# controller.net
KiCad netlist of a schematic drawn in Altium Designer
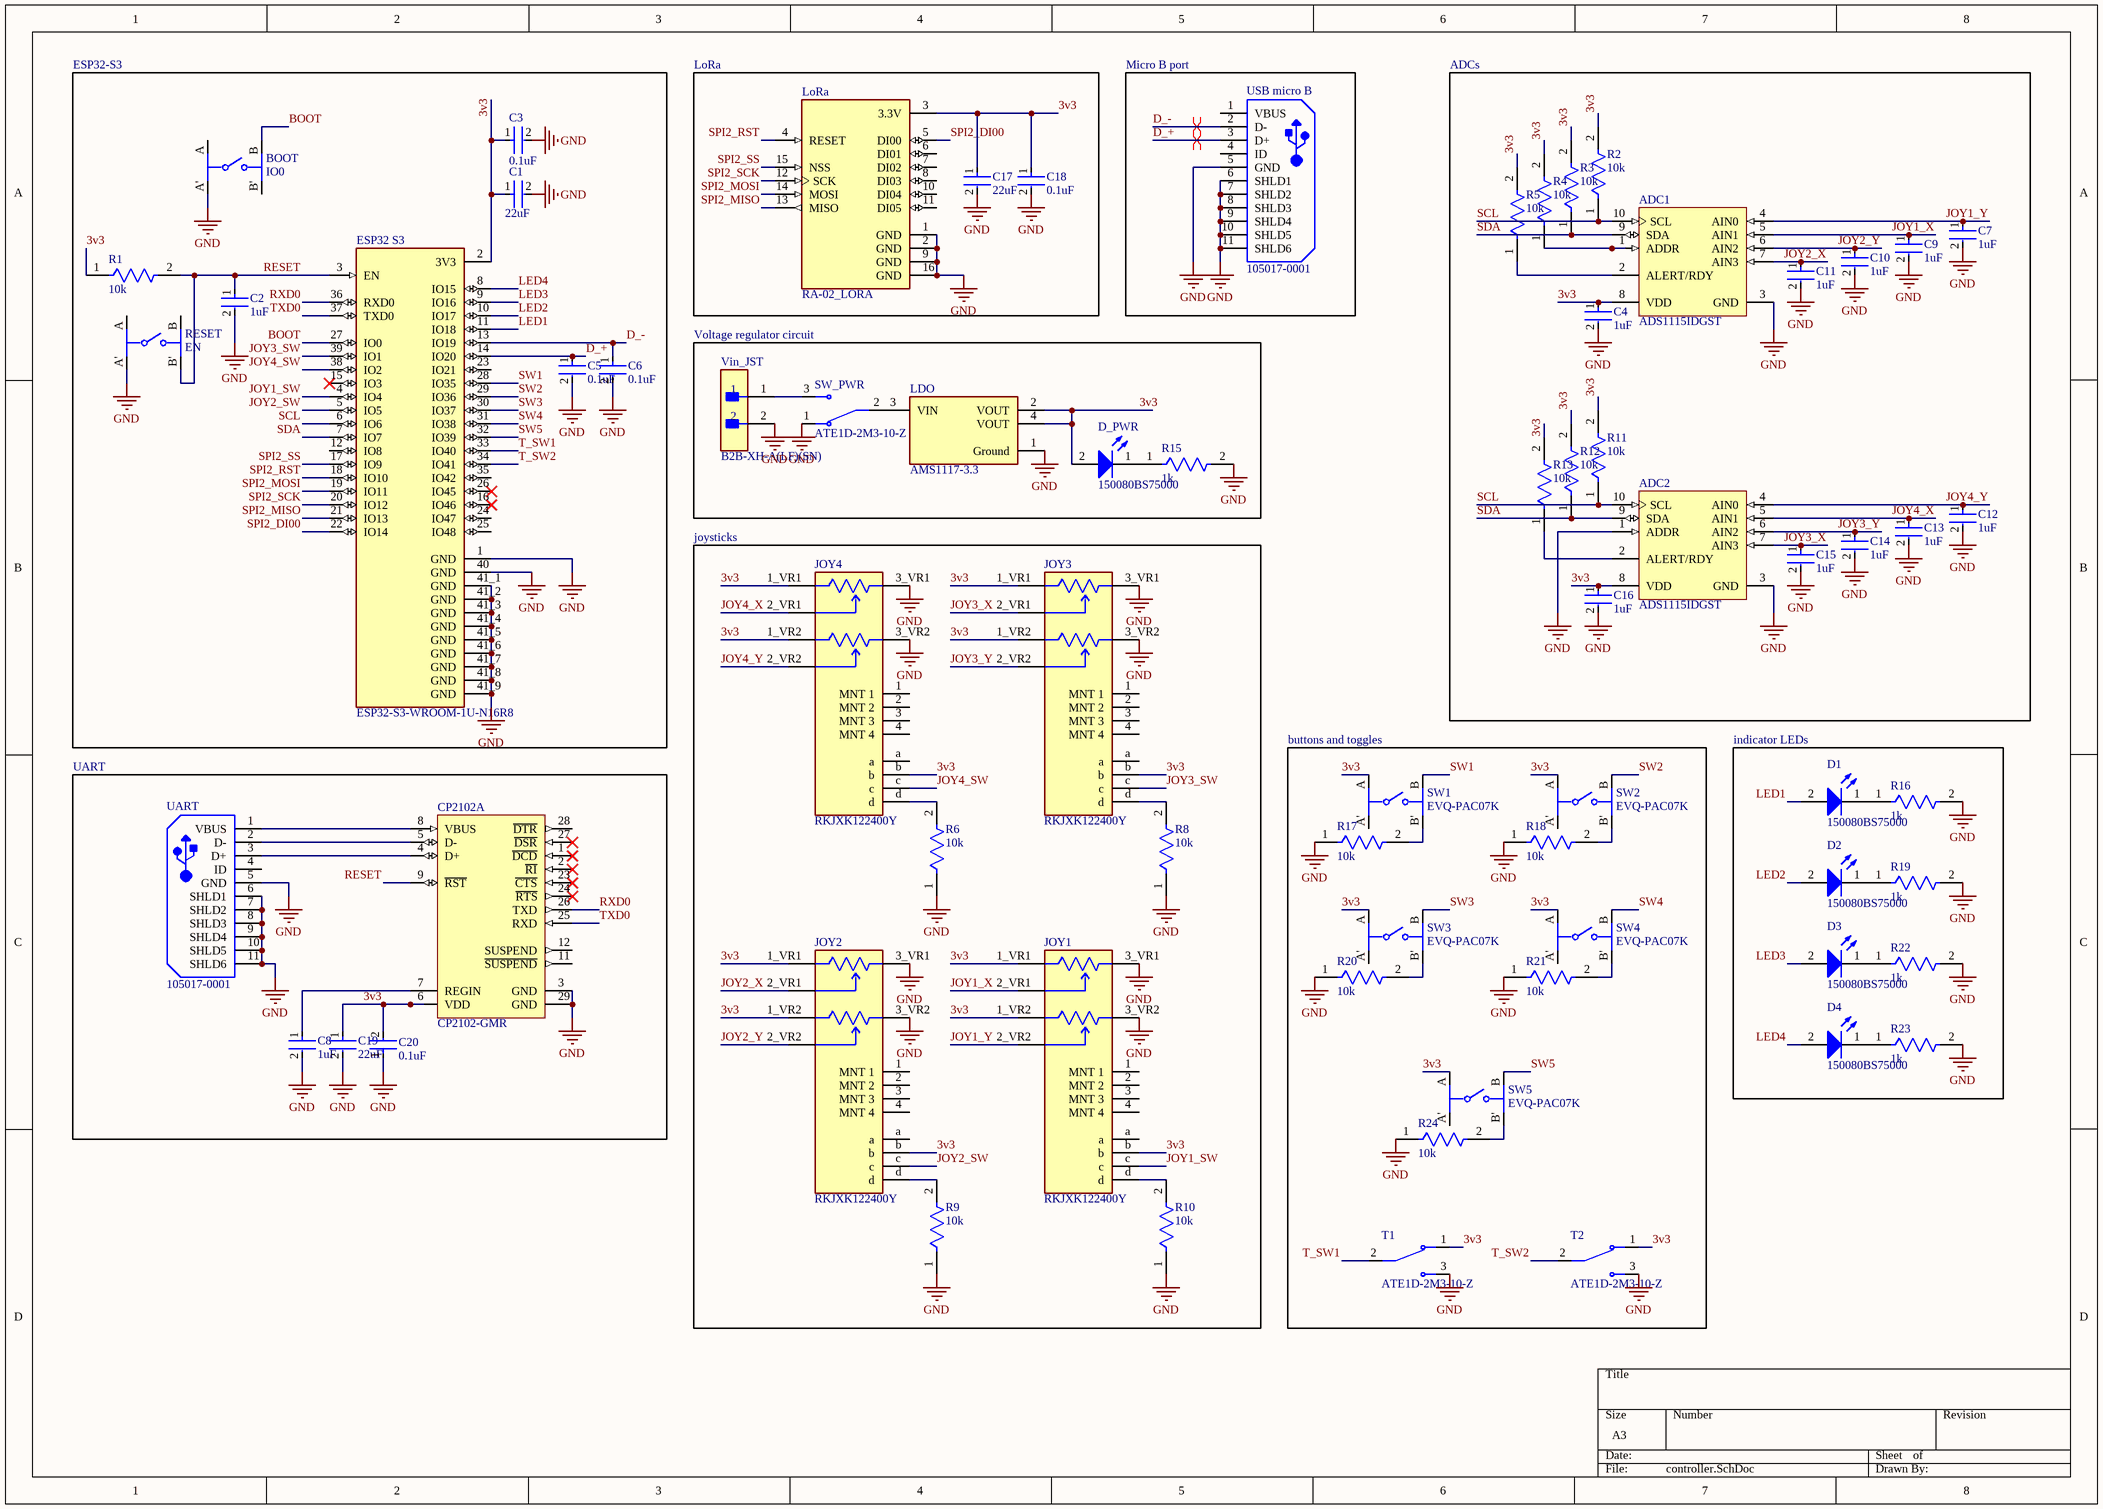
[diagram p0: controller.SchDoc]

(export (version "E")
  (design (tool "Eeschema 10.0.6"))
  (components
    (comp (ref "ADC1")
      (value "ADS1115IDGST")
      (footprint "TI-DGS10_M")
      (fields (field (name "MANUFACTURER") "Texas Instruments"))
      (libsource (lib "Altium Content Vault") (part "TI-ADS1015_1115-10"))
    )
    (comp (ref "ADC2")
      (value "ADS1115IDGST")
      (footprint "TI-DGS10_M")
      (fields (field (name "MANUFACTURER") "Texas Instruments"))
      (libsource (lib "Altium Content Vault") (part "TI-ADS1015_1115-10"))
    )
    (comp (ref "BOOT")
      (value "IO0")
      (footprint "FP-EVQ-PAC07K-MFG")
      (description "EVQ-PAC07K Switch Tactile N.O. SPST Round Button PC Pins 0.02A 15VDC 1N Thru-Hole Bulk")
      (libsource (lib "Altium Content Vault") (part "841f23923f71b23f3ea0ab5dfb78dcc"))
    )
    (comp (ref "C1")
      (value "22uF")
      (footprint "FP-0805-L_2_01_0_2-W_1_25-IPC_B")
      (description "General Purpose Ceramic Capacitor, 0805, 22uF, 20%, X5R, 15%, 6.3V")
      (fields (field (name "TOLERANCE") "20%") (field (name "VOLTAGE") "6.3V"))
      (libsource (lib "Altium Content Vault") (part "02cd4be3c70576c341d710602a673aa"))
    )
    (comp (ref "C2")
      (value "1uF")
      (footprint "FP-0805-L_2_01_0_2-W_1_25-IPC_B")
      (description "General Purpose Ceramic Capacitor, 0805, 1uF, 10%, X7R, 15%, 25V")
      (fields (field (name "TOLERANCE") "10%") (field (name "VOLTAGE") "25V"))
      (libsource (lib "Altium Content Vault") (part "b4654b650e69147ec39a6b967a45e02"))
    )
    (comp (ref "C3")
      (value "0.1uF")
      (footprint "FP-0805-L_2_01_0_2-W_1_25-IPC_C")
      (description "General Purpose Ceramic Capacitor, 0805, 100nF, 10%, X7R, 0.15, 50V")
      (fields (field (name "TOLERANCE") "10%") (field (name "VOLTAGE") "50V"))
      (libsource (lib "Altium Content Vault") (part "02cd4be3c70576c341d710602a673aa"))
    )
    (comp (ref "C4")
      (value "1uF")
      (footprint "FP-0805-L_2_01_0_2-W_1_25-IPC_B")
      (description "General Purpose Ceramic Capacitor, 0805, 1uF, 10%, X7R, 15%, 25V")
      (fields (field (name "TOLERANCE") "10%") (field (name "VOLTAGE") "25V"))
      (libsource (lib "Altium Content Vault") (part "b4654b650e69147ec39a6b967a45e02"))
    )
    (comp (ref "C5")
      (value "0.1uF")
      (footprint "FP-0805-L_2_01_0_2-W_1_25-IPC_C")
      (description "General Purpose Ceramic Capacitor, 0805, 100nF, 10%, X7R, 0.15, 50V")
      (fields (field (name "TOLERANCE") "10%") (field (name "VOLTAGE") "50V"))
      (libsource (lib "Altium Content Vault") (part "02cd4be3c70576c341d710602a673aa"))
    )
    (comp (ref "C6")
      (value "0.1uF")
      (footprint "FP-0805-L_2_01_0_2-W_1_25-IPC_C")
      (description "General Purpose Ceramic Capacitor, 0805, 100nF, 10%, X7R, 0.15, 50V")
      (fields (field (name "TOLERANCE") "10%") (field (name "VOLTAGE") "50V"))
      (libsource (lib "Altium Content Vault") (part "02cd4be3c70576c341d710602a673aa"))
    )
    (comp (ref "C7")
      (value "1uF")
      (footprint "FP-0805-L_2_01_0_2-W_1_25-IPC_B")
      (description "General Purpose Ceramic Capacitor, 0805, 1uF, 10%, X7R, 15%, 25V")
      (fields (field (name "TOLERANCE") "10%") (field (name "VOLTAGE") "25V"))
      (libsource (lib "Altium Content Vault") (part "b4654b650e69147ec39a6b967a45e02"))
    )
    (comp (ref "C8")
      (value "1uF")
      (footprint "FP-0805-L_2_01_0_2-W_1_25-IPC_B")
      (description "General Purpose Ceramic Capacitor, 0805, 1uF, 10%, X7R, 15%, 25V")
      (fields (field (name "TOLERANCE") "10%") (field (name "VOLTAGE") "25V"))
      (libsource (lib "Altium Content Vault") (part "b4654b650e69147ec39a6b967a45e02"))
    )
    (comp (ref "C9")
      (value "1uF")
      (footprint "FP-0805-L_2_01_0_2-W_1_25-IPC_B")
      (description "General Purpose Ceramic Capacitor, 0805, 1uF, 10%, X7R, 15%, 25V")
      (fields (field (name "TOLERANCE") "10%") (field (name "VOLTAGE") "25V"))
      (libsource (lib "Altium Content Vault") (part "b4654b650e69147ec39a6b967a45e02"))
    )
    (comp (ref "C10")
      (value "1uF")
      (footprint "FP-0805-L_2_01_0_2-W_1_25-IPC_B")
      (description "General Purpose Ceramic Capacitor, 0805, 1uF, 10%, X7R, 15%, 25V")
      (fields (field (name "TOLERANCE") "10%") (field (name "VOLTAGE") "25V"))
      (libsource (lib "Altium Content Vault") (part "b4654b650e69147ec39a6b967a45e02"))
    )
    (comp (ref "C11")
      (value "1uF")
      (footprint "FP-0805-L_2_01_0_2-W_1_25-IPC_B")
      (description "General Purpose Ceramic Capacitor, 0805, 1uF, 10%, X7R, 15%, 25V")
      (fields (field (name "TOLERANCE") "10%") (field (name "VOLTAGE") "25V"))
      (libsource (lib "Altium Content Vault") (part "b4654b650e69147ec39a6b967a45e02"))
    )
    (comp (ref "C12")
      (value "1uF")
      (footprint "FP-0805-L_2_01_0_2-W_1_25-IPC_B")
      (description "General Purpose Ceramic Capacitor, 0805, 1uF, 10%, X7R, 15%, 25V")
      (fields (field (name "TOLERANCE") "10%") (field (name "VOLTAGE") "25V"))
      (libsource (lib "Altium Content Vault") (part "b4654b650e69147ec39a6b967a45e02"))
    )
    (comp (ref "C13")
      (value "1uF")
      (footprint "FP-0805-L_2_01_0_2-W_1_25-IPC_B")
      (description "General Purpose Ceramic Capacitor, 0805, 1uF, 10%, X7R, 15%, 25V")
      (fields (field (name "TOLERANCE") "10%") (field (name "VOLTAGE") "25V"))
      (libsource (lib "Altium Content Vault") (part "b4654b650e69147ec39a6b967a45e02"))
    )
    (comp (ref "C14")
      (value "1uF")
      (footprint "FP-0805-L_2_01_0_2-W_1_25-IPC_B")
      (description "General Purpose Ceramic Capacitor, 0805, 1uF, 10%, X7R, 15%, 25V")
      (fields (field (name "TOLERANCE") "10%") (field (name "VOLTAGE") "25V"))
      (libsource (lib "Altium Content Vault") (part "b4654b650e69147ec39a6b967a45e02"))
    )
    (comp (ref "C15")
      (value "1uF")
      (footprint "FP-0805-L_2_01_0_2-W_1_25-IPC_B")
      (description "General Purpose Ceramic Capacitor, 0805, 1uF, 10%, X7R, 15%, 25V")
      (fields (field (name "TOLERANCE") "10%") (field (name "VOLTAGE") "25V"))
      (libsource (lib "Altium Content Vault") (part "b4654b650e69147ec39a6b967a45e02"))
    )
    (comp (ref "C16")
      (value "1uF")
      (footprint "FP-0805-L_2_01_0_2-W_1_25-IPC_B")
      (description "General Purpose Ceramic Capacitor, 0805, 1uF, 10%, X7R, 15%, 25V")
      (fields (field (name "TOLERANCE") "10%") (field (name "VOLTAGE") "25V"))
      (libsource (lib "Altium Content Vault") (part "b4654b650e69147ec39a6b967a45e02"))
    )
    (comp (ref "C17")
      (value "22uF")
      (footprint "FP-0805-L_2_01_0_2-W_1_25-IPC_B")
      (description "General Purpose Ceramic Capacitor, 0805, 22uF, 20%, X5R, 15%, 6.3V")
      (fields (field (name "TOLERANCE") "20%") (field (name "VOLTAGE") "6.3V"))
      (libsource (lib "Altium Content Vault") (part "02cd4be3c70576c341d710602a673aa"))
    )
    (comp (ref "C18")
      (value "0.1uF")
      (footprint "FP-0805-L_2_01_0_2-W_1_25-IPC_C")
      (description "General Purpose Ceramic Capacitor, 0805, 100nF, 10%, X7R, 0.15, 50V")
      (fields (field (name "TOLERANCE") "10%") (field (name "VOLTAGE") "50V"))
      (libsource (lib "Altium Content Vault") (part "02cd4be3c70576c341d710602a673aa"))
    )
    (comp (ref "C19")
      (value "22uF")
      (footprint "FP-0805-L_2_01_0_2-W_1_25-IPC_B")
      (description "General Purpose Ceramic Capacitor, 0805, 22uF, 20%, X5R, 15%, 6.3V")
      (fields (field (name "TOLERANCE") "20%") (field (name "VOLTAGE") "6.3V"))
      (libsource (lib "Altium Content Vault") (part "02cd4be3c70576c341d710602a673aa"))
    )
    (comp (ref "C20")
      (value "0.1uF")
      (footprint "FP-0805-L_2_01_0_2-W_1_25-IPC_C")
      (description "General Purpose Ceramic Capacitor, 0805, 100nF, 10%, X7R, 0.15, 50V")
      (fields (field (name "TOLERANCE") "10%") (field (name "VOLTAGE") "50V"))
      (libsource (lib "Altium Content Vault") (part "02cd4be3c70576c341d710602a673aa"))
    )
    (comp (ref "CP2102")
      (value "CP2102-GMR")
      (footprint "SLAB-QFN-28-3125x3125TP_M")
      (description "Single-Chip USB to URAT Bridge, 3.3 V, -40 to 85 degC, 28-Pin QFN, RoHS, Tape and Reel")
      (fields (field (name "MANUFACTURER") "Silicon Labs"))
      (libsource (lib "Altium Content Vault") (part "SLAB-CP210X-QFN-28-29"))
    )
    (comp (ref "D1")
      (value "150080BS75000")
      (footprint "WL-SMCW_0805_150080xx75000")
      (description "Led, Blue, 470 Nm, 3.2 V, 30 Ma, 145 Mcd Rohs Compliant: Yes")
      (libsource (lib "Altium Content Vault") (part "LED_Blue_2A-1K"))
    )
    (comp (ref "D2")
      (value "150080BS75000")
      (footprint "WL-SMCW_0805_150080xx75000")
      (description "Led, Blue, 470 Nm, 3.2 V, 30 Ma, 145 Mcd Rohs Compliant: Yes")
      (libsource (lib "Altium Content Vault") (part "LED_Blue_2A-1K"))
    )
    (comp (ref "D3")
      (value "150080BS75000")
      (footprint "WL-SMCW_0805_150080xx75000")
      (description "Led, Blue, 470 Nm, 3.2 V, 30 Ma, 145 Mcd Rohs Compliant: Yes")
      (libsource (lib "Altium Content Vault") (part "LED_Blue_2A-1K"))
    )
    (comp (ref "D4")
      (value "150080BS75000")
      (footprint "WL-SMCW_0805_150080xx75000")
      (description "Led, Blue, 470 Nm, 3.2 V, 30 Ma, 145 Mcd Rohs Compliant: Yes")
      (libsource (lib "Altium Content Vault") (part "LED_Blue_2A-1K"))
    )
    (comp (ref "D_PWR")
      (value "150080BS75000")
      (footprint "WL-SMCW_0805_150080xx75000")
      (description "Led, Blue, 470 Nm, 3.2 V, 30 Ma, 145 Mcd Rohs Compliant: Yes")
      (libsource (lib "Altium Content Vault") (part "LED_Blue_2A-1K"))
    )
    (comp (ref "ESP32 S3")
      (value "ESP32-S3-WROOM-1U-N16R8")
      (footprint "XCVR_ESP32-S3-WROOM-1U-N16R8")
      (fields (field (name "MF") "Espressif Systems"))
      (libsource (lib "ESP32-S3-WROOM-1U-N16R8") (part "ESP32-S3-WROOM-1U-N16R8"))
    )
    (comp (ref "JOY1")
      (value "RKJXK122400Y")
      (footprint "FP-RKJXK122400Y-MFG")
      (description "Res POT 10K Ohm 0.0125W (25.4 X 20.7 X 19.3mm) Pin Bracket Mount/Through Hole Tray")
      (libsource (lib "Altium Content Vault") (part "63a56dd8e99e1e1552a3870b2e96c5c"))
    )
    (comp (ref "JOY2")
      (value "RKJXK122400Y")
      (footprint "FP-RKJXK122400Y-MFG")
      (description "Res POT 10K Ohm 0.0125W (25.4 X 20.7 X 19.3mm) Pin Bracket Mount/Through Hole Tray")
      (libsource (lib "Altium Content Vault") (part "63a56dd8e99e1e1552a3870b2e96c5c"))
    )
    (comp (ref "JOY3")
      (value "RKJXK122400Y")
      (footprint "FP-RKJXK122400Y-MFG")
      (description "Res POT 10K Ohm 0.0125W (25.4 X 20.7 X 19.3mm) Pin Bracket Mount/Through Hole Tray")
      (libsource (lib "Altium Content Vault") (part "63a56dd8e99e1e1552a3870b2e96c5c"))
    )
    (comp (ref "JOY4")
      (value "RKJXK122400Y")
      (footprint "FP-RKJXK122400Y-MFG")
      (description "Res POT 10K Ohm 0.0125W (25.4 X 20.7 X 19.3mm) Pin Bracket Mount/Through Hole Tray")
      (libsource (lib "Altium Content Vault") (part "63a56dd8e99e1e1552a3870b2e96c5c"))
    )
    (comp (ref "LDO")
      (value "AMS1117-3.3")
      (footprint "FP-AMS1117-IPC_C")
      (description "LDO Voltage Regulators 1A, 3.3V")
      (fields
        (field (name "OCTOPART") "https://octopart.com/ams1117-3.3-advanced+monolithic+systems-25899300")
        (field (name "MANUFACTURER") "Advanced Monolithic Systems")
      )
      (libsource (lib "Altium Content Vault") (part "8bdbb5f8e77002000e30dd2845d0354"))
    )
    (comp (ref "LoRa")
      (value "RA-02_LORA")
      (footprint "MODULE_RA-02_LORA")
      (description "Ra-02 LoRa RF M5Stack Platform Evaluation Expansion Board")
      (libsource (lib "RA-02_LORA") (part "RA-02_LORA"))
    )
    (comp (ref "R1")
      (value "10k")
      (footprint "FP-CRCW0805-e3-IPC_A")
      (description "RES Thick Film, 10kΩ, 1%, 0.125W, 100ppm/°C, 0805")
      (fields (field (name "TOLERANCE") "1%"))
      (libsource (lib "Altium Content Vault") (part "1029c3af85768c4190bb7ad29bc67b5"))
    )
    (comp (ref "R2")
      (value "10k")
      (footprint "FP-CRCW0805-e3-IPC_A")
      (description "RES Thick Film, 10kΩ, 1%, 0.125W, 100ppm/°C, 0805")
      (fields (field (name "TOLERANCE") "1%"))
      (libsource (lib "Altium Content Vault") (part "1029c3af85768c4190bb7ad29bc67b5"))
    )
    (comp (ref "R3")
      (value "10k")
      (footprint "FP-CRCW0805-e3-IPC_A")
      (description "RES Thick Film, 10kΩ, 1%, 0.125W, 100ppm/°C, 0805")
      (fields (field (name "TOLERANCE") "1%"))
      (libsource (lib "Altium Content Vault") (part "1029c3af85768c4190bb7ad29bc67b5"))
    )
    (comp (ref "R4")
      (value "10k")
      (footprint "FP-CRCW0805-e3-IPC_A")
      (description "RES Thick Film, 10kΩ, 1%, 0.125W, 100ppm/°C, 0805")
      (fields (field (name "TOLERANCE") "1%"))
      (libsource (lib "Altium Content Vault") (part "1029c3af85768c4190bb7ad29bc67b5"))
    )
    (comp (ref "R5")
      (value "10k")
      (footprint "FP-CRCW0805-e3-IPC_A")
      (description "RES Thick Film, 10kΩ, 1%, 0.125W, 100ppm/°C, 0805")
      (fields (field (name "TOLERANCE") "1%"))
      (libsource (lib "Altium Content Vault") (part "1029c3af85768c4190bb7ad29bc67b5"))
    )
    (comp (ref "R6")
      (value "10k")
      (footprint "FP-CRCW0805-e3-IPC_A")
      (description "RES Thick Film, 10kΩ, 1%, 0.125W, 100ppm/°C, 0805")
      (fields (field (name "TOLERANCE") "1%"))
      (libsource (lib "Altium Content Vault") (part "1029c3af85768c4190bb7ad29bc67b5"))
    )
    (comp (ref "R8")
      (value "10k")
      (footprint "FP-CRCW0805-e3-IPC_A")
      (description "RES Thick Film, 10kΩ, 1%, 0.125W, 100ppm/°C, 0805")
      (fields (field (name "TOLERANCE") "1%"))
      (libsource (lib "Altium Content Vault") (part "1029c3af85768c4190bb7ad29bc67b5"))
    )
    (comp (ref "R9")
      (value "10k")
      (footprint "FP-CRCW0805-e3-IPC_A")
      (description "RES Thick Film, 10kΩ, 1%, 0.125W, 100ppm/°C, 0805")
      (fields (field (name "TOLERANCE") "1%"))
      (libsource (lib "Altium Content Vault") (part "1029c3af85768c4190bb7ad29bc67b5"))
    )
    (comp (ref "R10")
      (value "10k")
      (footprint "FP-CRCW0805-e3-IPC_A")
      (description "RES Thick Film, 10kΩ, 1%, 0.125W, 100ppm/°C, 0805")
      (fields (field (name "TOLERANCE") "1%"))
      (libsource (lib "Altium Content Vault") (part "1029c3af85768c4190bb7ad29bc67b5"))
    )
    (comp (ref "R11")
      (value "10k")
      (footprint "FP-CRCW0805-e3-IPC_A")
      (description "RES Thick Film, 10kΩ, 1%, 0.125W, 100ppm/°C, 0805")
      (fields (field (name "TOLERANCE") "1%"))
      (libsource (lib "Altium Content Vault") (part "1029c3af85768c4190bb7ad29bc67b5"))
    )
    (comp (ref "R12")
      (value "10k")
      (footprint "FP-CRCW0805-e3-IPC_A")
      (description "RES Thick Film, 10kΩ, 1%, 0.125W, 100ppm/°C, 0805")
      (fields (field (name "TOLERANCE") "1%"))
      (libsource (lib "Altium Content Vault") (part "1029c3af85768c4190bb7ad29bc67b5"))
    )
    (comp (ref "R13")
      (value "10k")
      (footprint "FP-CRCW0805-e3-IPC_A")
      (description "RES Thick Film, 10kΩ, 1%, 0.125W, 100ppm/°C, 0805")
      (fields (field (name "TOLERANCE") "1%"))
      (libsource (lib "Altium Content Vault") (part "1029c3af85768c4190bb7ad29bc67b5"))
    )
    (comp (ref "R15")
      (value "1k")
      (footprint "FP-CRCW0805-e3-MFG")
      (description "RES Thick Film, 1.2kΩ, 1%, 0.125W, 100ppm/°C, 0805")
      (fields (field (name "TOLERANCE") "1%"))
      (libsource (lib "Altium Content Vault") (part "1029c3af85768c4190bb7ad29bc67b5"))
    )
    (comp (ref "R16")
      (value "1k")
      (footprint "FP-CRCW0805-e3-MFG")
      (description "RES Thick Film, 1.2kΩ, 1%, 0.125W, 100ppm/°C, 0805")
      (fields (field (name "TOLERANCE") "1%"))
      (libsource (lib "Altium Content Vault") (part "1029c3af85768c4190bb7ad29bc67b5"))
    )
    (comp (ref "R17")
      (value "10k")
      (footprint "FP-CRCW0805-e3-IPC_A")
      (description "RES Thick Film, 10kΩ, 1%, 0.125W, 100ppm/°C, 0805")
      (fields (field (name "TOLERANCE") "1%"))
      (libsource (lib "Altium Content Vault") (part "1029c3af85768c4190bb7ad29bc67b5"))
    )
    (comp (ref "R18")
      (value "10k")
      (footprint "FP-CRCW0805-e3-IPC_A")
      (description "RES Thick Film, 10kΩ, 1%, 0.125W, 100ppm/°C, 0805")
      (fields (field (name "TOLERANCE") "1%"))
      (libsource (lib "Altium Content Vault") (part "1029c3af85768c4190bb7ad29bc67b5"))
    )
    (comp (ref "R19")
      (value "1k")
      (footprint "FP-CRCW0805-e3-MFG")
      (description "RES Thick Film, 1.2kΩ, 1%, 0.125W, 100ppm/°C, 0805")
      (fields (field (name "TOLERANCE") "1%"))
      (libsource (lib "Altium Content Vault") (part "1029c3af85768c4190bb7ad29bc67b5"))
    )
    (comp (ref "R20")
      (value "10k")
      (footprint "FP-CRCW0805-e3-IPC_A")
      (description "RES Thick Film, 10kΩ, 1%, 0.125W, 100ppm/°C, 0805")
      (fields (field (name "TOLERANCE") "1%"))
      (libsource (lib "Altium Content Vault") (part "1029c3af85768c4190bb7ad29bc67b5"))
    )
    (comp (ref "R21")
      (value "10k")
      (footprint "FP-CRCW0805-e3-IPC_A")
      (description "RES Thick Film, 10kΩ, 1%, 0.125W, 100ppm/°C, 0805")
      (fields (field (name "TOLERANCE") "1%"))
      (libsource (lib "Altium Content Vault") (part "1029c3af85768c4190bb7ad29bc67b5"))
    )
    (comp (ref "R22")
      (value "1k")
      (footprint "FP-CRCW0805-e3-MFG")
      (description "RES Thick Film, 1.2kΩ, 1%, 0.125W, 100ppm/°C, 0805")
      (fields (field (name "TOLERANCE") "1%"))
      (libsource (lib "Altium Content Vault") (part "1029c3af85768c4190bb7ad29bc67b5"))
    )
    (comp (ref "R23")
      (value "1k")
      (footprint "FP-CRCW0805-e3-MFG")
      (description "RES Thick Film, 1.2kΩ, 1%, 0.125W, 100ppm/°C, 0805")
      (fields (field (name "TOLERANCE") "1%"))
      (libsource (lib "Altium Content Vault") (part "1029c3af85768c4190bb7ad29bc67b5"))
    )
    (comp (ref "R24")
      (value "10k")
      (footprint "FP-CRCW0805-e3-IPC_A")
      (description "RES Thick Film, 10kΩ, 1%, 0.125W, 100ppm/°C, 0805")
      (fields (field (name "TOLERANCE") "1%"))
      (libsource (lib "Altium Content Vault") (part "1029c3af85768c4190bb7ad29bc67b5"))
    )
    (comp (ref "RESET")
      (value "EN")
      (footprint "FP-EVQ-PAC07K-MFG")
      (description "EVQ-PAC07K Switch Tactile N.O. SPST Round Button PC Pins 0.02A 15VDC 1N Thru-Hole Bulk")
      (libsource (lib "Altium Content Vault") (part "841f23923f71b23f3ea0ab5dfb78dcc"))
    )
    (comp (ref "SW1")
      (value "EVQ-PAC07K")
      (footprint "FP-EVQ-PAC07K-MFG")
      (description "EVQ-PAC07K Switch Tactile N.O. SPST Round Button PC Pins 0.02A 15VDC 1N Thru-Hole Bulk")
      (libsource (lib "Altium Content Vault") (part "841f23923f71b23f3ea0ab5dfb78dcc"))
    )
    (comp (ref "SW2")
      (value "EVQ-PAC07K")
      (footprint "FP-EVQ-PAC07K-MFG")
      (description "EVQ-PAC07K Switch Tactile N.O. SPST Round Button PC Pins 0.02A 15VDC 1N Thru-Hole Bulk")
      (libsource (lib "Altium Content Vault") (part "841f23923f71b23f3ea0ab5dfb78dcc"))
    )
    (comp (ref "SW3")
      (value "EVQ-PAC07K")
      (footprint "FP-EVQ-PAC07K-MFG")
      (description "EVQ-PAC07K Switch Tactile N.O. SPST Round Button PC Pins 0.02A 15VDC 1N Thru-Hole Bulk")
      (libsource (lib "Altium Content Vault") (part "841f23923f71b23f3ea0ab5dfb78dcc"))
    )
    (comp (ref "SW4")
      (value "EVQ-PAC07K")
      (footprint "FP-EVQ-PAC07K-MFG")
      (description "EVQ-PAC07K Switch Tactile N.O. SPST Round Button PC Pins 0.02A 15VDC 1N Thru-Hole Bulk")
      (libsource (lib "Altium Content Vault") (part "841f23923f71b23f3ea0ab5dfb78dcc"))
    )
    (comp (ref "SW5")
      (value "EVQ-PAC07K")
      (footprint "FP-EVQ-PAC07K-MFG")
      (description "EVQ-PAC07K Switch Tactile N.O. SPST Round Button PC Pins 0.02A 15VDC 1N Thru-Hole Bulk")
      (libsource (lib "Altium Content Vault") (part "841f23923f71b23f3ea0ab5dfb78dcc"))
    )
    (comp (ref "SW_PWR")
      (value "ATE1D-2M3-10-Z")
      (footprint "SW_ATE1D-2M3-10-Z")
      (description "Toggle Switch SPDT Through Hole")
      (fields
        (field (name "MF") "Nidec Copal Electronics")
        (field (name "DIGI-KEY_PART_NUMBER") "563-1157-ND")
      )
      (libsource (lib "ATE1D-2M3-10-Z") (part "ATE1D-2M3-10-Z"))
    )
    (comp (ref "T1")
      (value "ATE1D-2M3-10-Z")
      (footprint "SW_ATE1D-2M3-10-Z")
      (description "Toggle Switch SPDT Through Hole")
      (fields
        (field (name "MF") "Nidec Copal Electronics")
        (field (name "DIGI-KEY_PART_NUMBER") "563-1157-ND")
      )
      (libsource (lib "ATE1D-2M3-10-Z") (part "ATE1D-2M3-10-Z"))
    )
    (comp (ref "T2")
      (value "ATE1D-2M3-10-Z")
      (footprint "SW_ATE1D-2M3-10-Z")
      (description "Toggle Switch SPDT Through Hole")
      (fields
        (field (name "MF") "Nidec Copal Electronics")
        (field (name "DIGI-KEY_PART_NUMBER") "563-1157-ND")
      )
      (libsource (lib "ATE1D-2M3-10-Z") (part "ATE1D-2M3-10-Z"))
    )
    (comp (ref "UART")
      (value "105017-0001")
      (footprint "USB-MICRO-B_V")
      (fields (field (name "MANUFACTURER") "Molex"))
      (libsource (lib "Altium Content Vault") (part "USB-5-6SHLD"))
    )
    (comp (ref "USB micro B")
      (value "105017-0001")
      (footprint "USB-MICRO-B_V")
      (fields (field (name "MANUFACTURER") "Molex"))
      (libsource (lib "") (part "USB-5-6SHLD_1"))
    )
    (comp (ref "Vin_JST")
      (value "B2B-XH-A(LF)(SN)")
      (footprint "FP-B2B-XH-A_LF_SN-MFG")
      (description "CONN HEADER VERT 2POS 2.5MM")
      (libsource (lib "Altium Content Vault") (part "3bc925449376181038e59eaffc5286c"))
    )
  )
  (nets
    (net (code "1") (name "/3v3") (class "Default")
      (node (ref "ADC1") (pin "8") (pinfunction "VDD_8") (pintype "power_in"))
      (node (ref "ADC2") (pin "8") (pinfunction "VDD_8") (pintype "power_in"))
      (node (ref "C1") (pin "1") (pinfunction "1_1") (pintype "passive"))
      (node (ref "C16") (pin "1") (pinfunction "1_1") (pintype "passive"))
      (node (ref "C17") (pin "1") (pinfunction "1_1") (pintype "passive"))
      (node (ref "C18") (pin "1") (pinfunction "1_1") (pintype "passive"))
      (node (ref "C19") (pin "1") (pinfunction "1_1") (pintype "passive"))
      (node (ref "C20") (pin "2") (pinfunction "2_2") (pintype "passive"))
      (node (ref "C3") (pin "1") (pinfunction "1_1") (pintype "passive"))
      (node (ref "C4") (pin "1") (pinfunction "1_1") (pintype "passive"))
      (node (ref "CP2102") (pin "6") (pinfunction "VDD_6") (pintype "power_in"))
      (node (ref "D_PWR") (pin "2") (pinfunction "A_2") (pintype "passive"))
      (node (ref "ESP32 S3") (pin "2") (pinfunction "3V3_2") (pintype "power_in"))
      (node (ref "JOY1") (pin "1_VR1") (pinfunction "1_VR1_1_VR1") (pintype "passive"))
      (node (ref "JOY1") (pin "1_VR2") (pinfunction "1_VR2_1_VR2") (pintype "passive"))
      (node (ref "JOY1") (pin "b") (pinfunction "b_b") (pintype "passive"))
      (node (ref "JOY2") (pin "1_VR1") (pinfunction "1_VR1_1_VR1") (pintype "passive"))
      (node (ref "JOY2") (pin "1_VR2") (pinfunction "1_VR2_1_VR2") (pintype "passive"))
      (node (ref "JOY2") (pin "b") (pinfunction "b_b") (pintype "passive"))
      (node (ref "JOY3") (pin "1_VR1") (pinfunction "1_VR1_1_VR1") (pintype "passive"))
      (node (ref "JOY3") (pin "1_VR2") (pinfunction "1_VR2_1_VR2") (pintype "passive"))
      (node (ref "JOY3") (pin "b") (pinfunction "b_b") (pintype "passive"))
      (node (ref "JOY4") (pin "1_VR1") (pinfunction "1_VR1_1_VR1") (pintype "passive"))
      (node (ref "JOY4") (pin "1_VR2") (pinfunction "1_VR2_1_VR2") (pintype "passive"))
      (node (ref "JOY4") (pin "b") (pinfunction "b_b") (pintype "passive"))
      (node (ref "LDO") (pin "2") (pinfunction "VOUT_2") (pintype "passive"))
      (node (ref "LDO") (pin "4") (pinfunction "VOUT_4") (pintype "passive"))
      (node (ref "LoRa") (pin "3") (pinfunction "3.3V_3") (pintype "power_in"))
      (node (ref "R1") (pin "1") (pinfunction "1_1") (pintype "passive"))
      (node (ref "R11") (pin "2") (pinfunction "2_2") (pintype "passive"))
      (node (ref "R12") (pin "2") (pinfunction "2_2") (pintype "passive"))
      (node (ref "R13") (pin "2") (pinfunction "2_2") (pintype "passive"))
      (node (ref "R2") (pin "2") (pinfunction "2_2") (pintype "passive"))
      (node (ref "R3") (pin "2") (pinfunction "2_2") (pintype "passive"))
      (node (ref "R4") (pin "2") (pinfunction "2_2") (pintype "passive"))
      (node (ref "R5") (pin "2") (pinfunction "2_2") (pintype "passive"))
      (node (ref "SW1") (pin "A") (pinfunction "A_A") (pintype "passive"))
      (node (ref "SW2") (pin "A") (pinfunction "A_A") (pintype "passive"))
      (node (ref "SW3") (pin "A") (pinfunction "A_A") (pintype "passive"))
      (node (ref "SW4") (pin "A") (pinfunction "A_A") (pintype "passive"))
      (node (ref "SW5") (pin "A") (pinfunction "A_A") (pintype "passive"))
      (node (ref "T1") (pin "1") (pinfunction "1_1") (pintype "passive"))
      (node (ref "T2") (pin "1") (pinfunction "1_1") (pintype "passive"))
    )
    (net (code "2") (name "/BOOT") (class "Default")
      (node (ref "BOOT") (pin "B") (pinfunction "B_B") (pintype "passive"))
      (node (ref "ESP32 S3") (pin "27") (pinfunction "IO0_27") (pintype "bidirectional"))
    )
    (net (code "3") (name "/D_+") (class "Default")
      (node (ref "C5") (pin "1") (pinfunction "1_1") (pintype "passive"))
      (node (ref "ESP32 S3") (pin "14") (pinfunction "IO20_14") (pintype "bidirectional"))
      (node (ref "USB micro B") (pin "3") (pinfunction "D+_3") (pintype "passive"))
    )
    (net (code "4") (name "/D_-") (class "Default")
      (node (ref "C6") (pin "1") (pinfunction "1_1") (pintype "passive"))
      (node (ref "ESP32 S3") (pin "13") (pinfunction "IO19_13") (pintype "bidirectional"))
      (node (ref "USB micro B") (pin "2") (pinfunction "D-_2") (pintype "passive"))
    )
    (net (code "5") (name "/JOY1_SW") (class "Default")
      (node (ref "ESP32 S3") (pin "4") (pinfunction "IO4_4") (pintype "bidirectional"))
      (node (ref "JOY1") (pin "c") (pinfunction "c_c") (pintype "passive"))
    )
    (net (code "6") (name "/JOY1_X") (class "Default")
      (node (ref "ADC1") (pin "5") (pinfunction "AIN1_5") (pintype "input"))
      (node (ref "C9") (pin "1") (pinfunction "1_1") (pintype "passive"))
      (node (ref "JOY1") (pin "2_VR1") (pinfunction "2_VR1_2_VR1") (pintype "passive"))
    )
    (net (code "7") (name "/JOY1_Y") (class "Default")
      (node (ref "ADC1") (pin "4") (pinfunction "AIN0_4") (pintype "input"))
      (node (ref "C7") (pin "1") (pinfunction "1_1") (pintype "passive"))
      (node (ref "JOY1") (pin "2_VR2") (pinfunction "2_VR2_2_VR2") (pintype "passive"))
    )
    (net (code "8") (name "/JOY2_SW") (class "Default")
      (node (ref "ESP32 S3") (pin "5") (pinfunction "IO5_5") (pintype "bidirectional"))
      (node (ref "JOY2") (pin "c") (pinfunction "c_c") (pintype "passive"))
    )
    (net (code "9") (name "/JOY2_X") (class "Default")
      (node (ref "ADC1") (pin "7") (pinfunction "AIN3_7") (pintype "input"))
      (node (ref "C11") (pin "1") (pinfunction "1_1") (pintype "passive"))
      (node (ref "JOY2") (pin "2_VR1") (pinfunction "2_VR1_2_VR1") (pintype "passive"))
    )
    (net (code "10") (name "/JOY2_Y") (class "Default")
      (node (ref "ADC1") (pin "6") (pinfunction "AIN2_6") (pintype "input"))
      (node (ref "C10") (pin "1") (pinfunction "1_1") (pintype "passive"))
      (node (ref "JOY2") (pin "2_VR2") (pinfunction "2_VR2_2_VR2") (pintype "passive"))
    )
    (net (code "11") (name "/JOY3_SW") (class "Default")
      (node (ref "ESP32 S3") (pin "39") (pinfunction "IO1_39") (pintype "bidirectional"))
      (node (ref "JOY3") (pin "c") (pinfunction "c_c") (pintype "passive"))
    )
    (net (code "12") (name "/JOY3_X") (class "Default")
      (node (ref "ADC2") (pin "7") (pinfunction "AIN3_7") (pintype "input"))
      (node (ref "C15") (pin "1") (pinfunction "1_1") (pintype "passive"))
      (node (ref "JOY3") (pin "2_VR1") (pinfunction "2_VR1_2_VR1") (pintype "passive"))
    )
    (net (code "13") (name "/JOY3_Y") (class "Default")
      (node (ref "ADC2") (pin "6") (pinfunction "AIN2_6") (pintype "input"))
      (node (ref "C14") (pin "1") (pinfunction "1_1") (pintype "passive"))
      (node (ref "JOY3") (pin "2_VR2") (pinfunction "2_VR2_2_VR2") (pintype "passive"))
    )
    (net (code "14") (name "/JOY4_SW") (class "Default")
      (node (ref "ESP32 S3") (pin "38") (pinfunction "IO2_38") (pintype "bidirectional"))
      (node (ref "JOY4") (pin "c") (pinfunction "c_c") (pintype "passive"))
    )
    (net (code "15") (name "/JOY4_X") (class "Default")
      (node (ref "ADC2") (pin "5") (pinfunction "AIN1_5") (pintype "input"))
      (node (ref "C13") (pin "1") (pinfunction "1_1") (pintype "passive"))
      (node (ref "JOY4") (pin "2_VR1") (pinfunction "2_VR1_2_VR1") (pintype "passive"))
    )
    (net (code "16") (name "/JOY4_Y") (class "Default")
      (node (ref "ADC2") (pin "4") (pinfunction "AIN0_4") (pintype "input"))
      (node (ref "C12") (pin "1") (pinfunction "1_1") (pintype "passive"))
      (node (ref "JOY4") (pin "2_VR2") (pinfunction "2_VR2_2_VR2") (pintype "passive"))
    )
    (net (code "17") (name "/LED1") (class "Default")
      (node (ref "D1") (pin "2") (pinfunction "A_2") (pintype "passive"))
      (node (ref "ESP32 S3") (pin "11") (pinfunction "IO18_11") (pintype "bidirectional"))
    )
    (net (code "18") (name "/LED2") (class "Default")
      (node (ref "D2") (pin "2") (pinfunction "A_2") (pintype "passive"))
      (node (ref "ESP32 S3") (pin "10") (pinfunction "IO17_10") (pintype "bidirectional"))
    )
    (net (code "19") (name "/LED3") (class "Default")
      (node (ref "D3") (pin "2") (pinfunction "A_2") (pintype "passive"))
      (node (ref "ESP32 S3") (pin "9") (pinfunction "IO16_9") (pintype "bidirectional"))
    )
    (net (code "20") (name "/LED4") (class "Default")
      (node (ref "D4") (pin "2") (pinfunction "A_2") (pintype "passive"))
      (node (ref "ESP32 S3") (pin "8") (pinfunction "IO15_8") (pintype "bidirectional"))
    )
    (net (code "21") (name "/RESET") (class "Default")
      (node (ref "C2") (pin "1") (pinfunction "1_1") (pintype "passive"))
      (node (ref "CP2102") (pin "9") (pinfunction "~{RST}_9") (pintype "bidirectional"))
      (node (ref "ESP32 S3") (pin "3") (pinfunction "EN_3") (pintype "input"))
      (node (ref "R1") (pin "2") (pinfunction "2_2") (pintype "passive"))
      (node (ref "RESET") (pin "B'") (pinfunction "B'_B'") (pintype "passive"))
    )
    (net (code "22") (name "/RXD0") (class "Default")
      (node (ref "CP2102") (pin "26") (pinfunction "TXD_26") (pintype "output"))
      (node (ref "ESP32 S3") (pin "36") (pinfunction "RXD0_36") (pintype "bidirectional"))
    )
    (net (code "23") (name "/SCL") (class "Default")
      (node (ref "ADC1") (pin "10") (pinfunction "SCL_10") (pintype "input"))
      (node (ref "ADC2") (pin "10") (pinfunction "SCL_10") (pintype "input"))
      (node (ref "ESP32 S3") (pin "6") (pinfunction "IO6_6") (pintype "bidirectional"))
      (node (ref "R11") (pin "1") (pinfunction "1_1") (pintype "passive"))
      (node (ref "R2") (pin "1") (pinfunction "1_1") (pintype "passive"))
    )
    (net (code "24") (name "/SDA") (class "Default")
      (node (ref "ADC1") (pin "9") (pinfunction "SDA_9") (pintype "bidirectional"))
      (node (ref "ADC2") (pin "9") (pinfunction "SDA_9") (pintype "bidirectional"))
      (node (ref "ESP32 S3") (pin "7") (pinfunction "IO7_7") (pintype "bidirectional"))
      (node (ref "R12") (pin "1") (pinfunction "1_1") (pintype "passive"))
      (node (ref "R3") (pin "1") (pinfunction "1_1") (pintype "passive"))
    )
    (net (code "25") (name "/SPI2_DI00") (class "Default")
      (node (ref "ESP32 S3") (pin "22") (pinfunction "IO14_22") (pintype "bidirectional"))
      (node (ref "LoRa") (pin "5") (pinfunction "DI00_5") (pintype "bidirectional"))
    )
    (net (code "26") (name "/SPI2_MISO") (class "Default")
      (node (ref "ESP32 S3") (pin "21") (pinfunction "IO13_21") (pintype "bidirectional"))
      (node (ref "LoRa") (pin "13") (pinfunction "MISO_13") (pintype "output"))
    )
    (net (code "27") (name "/SPI2_MOSI") (class "Default")
      (node (ref "ESP32 S3") (pin "19") (pinfunction "IO11_19") (pintype "bidirectional"))
      (node (ref "LoRa") (pin "14") (pinfunction "MOSI_14") (pintype "input"))
    )
    (net (code "28") (name "/SPI2_RST") (class "Default")
      (node (ref "ESP32 S3") (pin "18") (pinfunction "IO10_18") (pintype "bidirectional"))
      (node (ref "LoRa") (pin "4") (pinfunction "RESET_4") (pintype "input"))
    )
    (net (code "29") (name "/SPI2_SCK") (class "Default")
      (node (ref "ESP32 S3") (pin "20") (pinfunction "IO12_20") (pintype "bidirectional"))
      (node (ref "LoRa") (pin "12") (pinfunction "SCK_12") (pintype "input"))
    )
    (net (code "30") (name "/SPI2_SS") (class "Default")
      (node (ref "ESP32 S3") (pin "17") (pinfunction "IO9_17") (pintype "bidirectional"))
      (node (ref "LoRa") (pin "15") (pinfunction "NSS_15") (pintype "input"))
    )
    (net (code "31") (name "/SW1") (class "Default")
      (node (ref "ESP32 S3") (pin "28") (pinfunction "IO35_28") (pintype "bidirectional"))
      (node (ref "SW1") (pin "B") (pinfunction "B_B") (pintype "passive"))
    )
    (net (code "32") (name "/SW2") (class "Default")
      (node (ref "ESP32 S3") (pin "29") (pinfunction "IO36_29") (pintype "bidirectional"))
      (node (ref "SW2") (pin "B") (pinfunction "B_B") (pintype "passive"))
    )
    (net (code "33") (name "/SW3") (class "Default")
      (node (ref "ESP32 S3") (pin "30") (pinfunction "IO37_30") (pintype "bidirectional"))
      (node (ref "SW3") (pin "B") (pinfunction "B_B") (pintype "passive"))
    )
    (net (code "34") (name "/SW4") (class "Default")
      (node (ref "ESP32 S3") (pin "31") (pinfunction "IO38_31") (pintype "bidirectional"))
      (node (ref "SW4") (pin "B") (pinfunction "B_B") (pintype "passive"))
    )
    (net (code "35") (name "/SW5") (class "Default")
      (node (ref "ESP32 S3") (pin "32") (pinfunction "IO39_32") (pintype "bidirectional"))
      (node (ref "SW5") (pin "B") (pinfunction "B_B") (pintype "passive"))
    )
    (net (code "36") (name "/TXD0") (class "Default")
      (node (ref "CP2102") (pin "25") (pinfunction "RXD_25") (pintype "input"))
      (node (ref "ESP32 S3") (pin "37") (pinfunction "TXD0_37") (pintype "bidirectional"))
    )
    (net (code "37") (name "/T_SW1") (class "Default")
      (node (ref "ESP32 S3") (pin "33") (pinfunction "IO40_33") (pintype "bidirectional"))
      (node (ref "T1") (pin "2") (pinfunction "2_2") (pintype "passive"))
    )
    (net (code "38") (name "/T_SW2") (class "Default")
      (node (ref "ESP32 S3") (pin "34") (pinfunction "IO41_34") (pintype "bidirectional"))
      (node (ref "T2") (pin "2") (pinfunction "2_2") (pintype "passive"))
    )
    (net (code "39") (name "GND") (class "Default")
      (node (ref "ADC1") (pin "3") (pinfunction "GND_3") (pintype "power_in"))
      (node (ref "ADC2") (pin "1") (pinfunction "ADDR_1") (pintype "input"))
      (node (ref "ADC2") (pin "3") (pinfunction "GND_3") (pintype "power_in"))
      (node (ref "BOOT") (pin "A'") (pinfunction "A'_A'") (pintype "passive"))
      (node (ref "C1") (pin "2") (pinfunction "2_2") (pintype "passive"))
      (node (ref "C10") (pin "2") (pinfunction "2_2") (pintype "passive"))
      (node (ref "C11") (pin "2") (pinfunction "2_2") (pintype "passive"))
      (node (ref "C12") (pin "2") (pinfunction "2_2") (pintype "passive"))
      (node (ref "C13") (pin "2") (pinfunction "2_2") (pintype "passive"))
      (node (ref "C14") (pin "2") (pinfunction "2_2") (pintype "passive"))
      (node (ref "C15") (pin "2") (pinfunction "2_2") (pintype "passive"))
      (node (ref "C16") (pin "2") (pinfunction "2_2") (pintype "passive"))
      (node (ref "C17") (pin "2") (pinfunction "2_2") (pintype "passive"))
      (node (ref "C18") (pin "2") (pinfunction "2_2") (pintype "passive"))
      (node (ref "C19") (pin "2") (pinfunction "2_2") (pintype "passive"))
      (node (ref "C2") (pin "2") (pinfunction "2_2") (pintype "passive"))
      (node (ref "C20") (pin "1") (pinfunction "1_1") (pintype "passive"))
      (node (ref "C3") (pin "2") (pinfunction "2_2") (pintype "passive"))
      (node (ref "C4") (pin "2") (pinfunction "2_2") (pintype "passive"))
      (node (ref "C5") (pin "2") (pinfunction "2_2") (pintype "passive"))
      (node (ref "C6") (pin "2") (pinfunction "2_2") (pintype "passive"))
      (node (ref "C7") (pin "2") (pinfunction "2_2") (pintype "passive"))
      (node (ref "C8") (pin "2") (pinfunction "2_2") (pintype "passive"))
      (node (ref "C9") (pin "2") (pinfunction "2_2") (pintype "passive"))
      (node (ref "CP2102") (pin "29") (pinfunction "GND_29") (pintype "power_in"))
      (node (ref "CP2102") (pin "3") (pinfunction "GND_3") (pintype "power_in"))
      (node (ref "ESP32 S3") (pin "1") (pinfunction "GND_1") (pintype "power_in"))
      (node (ref "ESP32 S3") (pin "40") (pinfunction "GND_40") (pintype "power_in"))
      (node (ref "ESP32 S3") (pin "41_1") (pinfunction "GND_41_1") (pintype "power_in"))
      (node (ref "ESP32 S3") (pin "41_2") (pinfunction "GND_41_2") (pintype "power_in"))
      (node (ref "ESP32 S3") (pin "41_3") (pinfunction "GND_41_3") (pintype "power_in"))
      (node (ref "ESP32 S3") (pin "41_4") (pinfunction "GND_41_4") (pintype "power_in"))
      (node (ref "ESP32 S3") (pin "41_5") (pinfunction "GND_41_5") (pintype "power_in"))
      (node (ref "ESP32 S3") (pin "41_6") (pinfunction "GND_41_6") (pintype "power_in"))
      (node (ref "ESP32 S3") (pin "41_7") (pinfunction "GND_41_7") (pintype "power_in"))
      (node (ref "ESP32 S3") (pin "41_8") (pinfunction "GND_41_8") (pintype "power_in"))
      (node (ref "ESP32 S3") (pin "41_9") (pinfunction "GND_41_9") (pintype "power_in"))
      (node (ref "JOY1") (pin "3_VR1") (pinfunction "3_VR1_3_VR1") (pintype "passive"))
      (node (ref "JOY1") (pin "3_VR2") (pinfunction "3_VR2_3_VR2") (pintype "passive"))
      (node (ref "JOY2") (pin "3_VR1") (pinfunction "3_VR1_3_VR1") (pintype "passive"))
      (node (ref "JOY2") (pin "3_VR2") (pinfunction "3_VR2_3_VR2") (pintype "passive"))
      (node (ref "JOY3") (pin "3_VR1") (pinfunction "3_VR1_3_VR1") (pintype "passive"))
      (node (ref "JOY3") (pin "3_VR2") (pinfunction "3_VR2_3_VR2") (pintype "passive"))
      (node (ref "JOY4") (pin "3_VR1") (pinfunction "3_VR1_3_VR1") (pintype "passive"))
      (node (ref "JOY4") (pin "3_VR2") (pinfunction "3_VR2_3_VR2") (pintype "passive"))
      (node (ref "LDO") (pin "1") (pinfunction "Ground_1") (pintype "power_in"))
      (node (ref "LoRa") (pin "1") (pinfunction "GND_1") (pintype "power_in"))
      (node (ref "LoRa") (pin "16") (pinfunction "GND_16") (pintype "power_in"))
      (node (ref "LoRa") (pin "2") (pinfunction "GND_2") (pintype "power_in"))
      (node (ref "LoRa") (pin "9") (pinfunction "GND_9") (pintype "power_in"))
      (node (ref "R10") (pin "1") (pinfunction "1_1") (pintype "passive"))
      (node (ref "R15") (pin "2") (pinfunction "2_2") (pintype "passive"))
      (node (ref "R16") (pin "2") (pinfunction "2_2") (pintype "passive"))
      (node (ref "R17") (pin "1") (pinfunction "1_1") (pintype "passive"))
      (node (ref "R18") (pin "1") (pinfunction "1_1") (pintype "passive"))
      (node (ref "R19") (pin "2") (pinfunction "2_2") (pintype "passive"))
      (node (ref "R20") (pin "1") (pinfunction "1_1") (pintype "passive"))
      (node (ref "R21") (pin "1") (pinfunction "1_1") (pintype "passive"))
      (node (ref "R22") (pin "2") (pinfunction "2_2") (pintype "passive"))
      (node (ref "R23") (pin "2") (pinfunction "2_2") (pintype "passive"))
      (node (ref "R24") (pin "1") (pinfunction "1_1") (pintype "passive"))
      (node (ref "R6") (pin "1") (pinfunction "1_1") (pintype "passive"))
      (node (ref "R8") (pin "1") (pinfunction "1_1") (pintype "passive"))
      (node (ref "R9") (pin "1") (pinfunction "1_1") (pintype "passive"))
      (node (ref "RESET") (pin "A'") (pinfunction "A'_A'") (pintype "passive"))
      (node (ref "SW_PWR") (pin "1") (pinfunction "1_1") (pintype "passive"))
      (node (ref "T1") (pin "3") (pinfunction "3_3") (pintype "passive"))
      (node (ref "T2") (pin "3") (pinfunction "3_3") (pintype "passive"))
      (node (ref "UART") (pin "10") (pinfunction "SHLD5_10") (pintype "passive"))
      (node (ref "UART") (pin "11") (pinfunction "SHLD6_11") (pintype "passive"))
      (node (ref "UART") (pin "5") (pinfunction "GND_5") (pintype "passive"))
      (node (ref "UART") (pin "6") (pinfunction "SHLD1_6") (pintype "passive"))
      (node (ref "UART") (pin "7") (pinfunction "SHLD2_7") (pintype "passive"))
      (node (ref "UART") (pin "8") (pinfunction "SHLD3_8") (pintype "passive"))
      (node (ref "UART") (pin "9") (pinfunction "SHLD4_9") (pintype "passive"))
      (node (ref "USB micro B") (pin "10") (pinfunction "SHLD5_10") (pintype "passive"))
      (node (ref "USB micro B") (pin "11") (pinfunction "SHLD6_11") (pintype "passive"))
      (node (ref "USB micro B") (pin "5") (pinfunction "GND_5") (pintype "passive"))
      (node (ref "USB micro B") (pin "6") (pinfunction "SHLD1_6") (pintype "passive"))
      (node (ref "USB micro B") (pin "7") (pinfunction "SHLD2_7") (pintype "passive"))
      (node (ref "USB micro B") (pin "8") (pinfunction "SHLD3_8") (pintype "passive"))
      (node (ref "USB micro B") (pin "9") (pinfunction "SHLD4_9") (pintype "passive"))
      (node (ref "Vin_JST") (pin "2") (pinfunction "2_2") (pintype "passive"))
    )
    (net (code "40") (name "Net-(ADC1-ADDR)") (class "Default")
      (node (ref "ADC1") (pin "1") (pinfunction "ADDR_1") (pintype "input"))
      (node (ref "R4") (pin "1") (pinfunction "1_1") (pintype "passive"))
    )
    (net (code "41") (name "Net-(ADC1-ALERT{slash}RDY)") (class "Default")
      (node (ref "ADC1") (pin "2") (pinfunction "ALERT/RDY_2") (pintype "open_collector"))
      (node (ref "R5") (pin "1") (pinfunction "1_1") (pintype "passive"))
    )
    (net (code "42") (name "Net-(ADC2-ALERT{slash}RDY)") (class "Default")
      (node (ref "ADC2") (pin "2") (pinfunction "ALERT/RDY_2") (pintype "open_collector"))
      (node (ref "R13") (pin "1") (pinfunction "1_1") (pintype "passive"))
    )
    (net (code "43") (name "Net-(CP2102A-D+)") (class "Default")
      (node (ref "CP2102") (pin "4") (pinfunction "D+_4") (pintype "bidirectional"))
      (node (ref "UART") (pin "3") (pinfunction "D+_3") (pintype "passive"))
    )
    (net (code "44") (name "Net-(CP2102A-D-)") (class "Default")
      (node (ref "CP2102") (pin "5") (pinfunction "D-_5") (pintype "bidirectional"))
      (node (ref "UART") (pin "2") (pinfunction "D-_2") (pintype "passive"))
    )
    (net (code "45") (name "Net-(CP2102A-REGIN)") (class "Default")
      (node (ref "C8") (pin "1") (pinfunction "1_1") (pintype "passive"))
      (node (ref "CP2102") (pin "7") (pinfunction "REGIN_7") (pintype "power_in"))
    )
    (net (code "46") (name "Net-(CP2102A-VBUS)") (class "Default")
      (node (ref "CP2102") (pin "8") (pinfunction "VBUS_8") (pintype "input"))
      (node (ref "UART") (pin "1") (pinfunction "VBUS_1") (pintype "passive"))
    )
    (net (code "47") (name "Net-(D1-K)") (class "Default")
      (node (ref "D1") (pin "1") (pinfunction "K_1") (pintype "passive"))
      (node (ref "R16") (pin "1") (pinfunction "1_1") (pintype "passive"))
    )
    (net (code "48") (name "Net-(D2-K)") (class "Default")
      (node (ref "D2") (pin "1") (pinfunction "K_1") (pintype "passive"))
      (node (ref "R19") (pin "1") (pinfunction "1_1") (pintype "passive"))
    )
    (net (code "49") (name "Net-(D3-K)") (class "Default")
      (node (ref "D3") (pin "1") (pinfunction "K_1") (pintype "passive"))
      (node (ref "R22") (pin "1") (pinfunction "1_1") (pintype "passive"))
    )
    (net (code "50") (name "Net-(D4-K)") (class "Default")
      (node (ref "D4") (pin "1") (pinfunction "K_1") (pintype "passive"))
      (node (ref "R23") (pin "1") (pinfunction "1_1") (pintype "passive"))
    )
    (net (code "51") (name "Net-(D_PWR-K)") (class "Default")
      (node (ref "D_PWR") (pin "1") (pinfunction "K_1") (pintype "passive"))
      (node (ref "R15") (pin "1") (pinfunction "1_1") (pintype "passive"))
    )
    (net (code "52") (name "Net-(JOY1-Padd)") (class "Default")
      (node (ref "JOY1") (pin "d") (pinfunction "d_d") (pintype "passive"))
      (node (ref "R10") (pin "2") (pinfunction "2_2") (pintype "passive"))
    )
    (net (code "53") (name "Net-(JOY2-Padd)") (class "Default")
      (node (ref "JOY2") (pin "d") (pinfunction "d_d") (pintype "passive"))
      (node (ref "R9") (pin "2") (pinfunction "2_2") (pintype "passive"))
    )
    (net (code "54") (name "Net-(JOY3-Padd)") (class "Default")
      (node (ref "JOY3") (pin "d") (pinfunction "d_d") (pintype "passive"))
      (node (ref "R8") (pin "2") (pinfunction "2_2") (pintype "passive"))
    )
    (net (code "55") (name "Net-(JOY4-Padd)") (class "Default")
      (node (ref "JOY4") (pin "d") (pinfunction "d_d") (pintype "passive"))
      (node (ref "R6") (pin "2") (pinfunction "2_2") (pintype "passive"))
    )
    (net (code "56") (name "Net-(LDO-VIN)") (class "Default")
      (node (ref "LDO") (pin "3") (pinfunction "VIN_3") (pintype "power_in"))
      (node (ref "SW_PWR") (pin "2") (pinfunction "2_2") (pintype "passive"))
    )
    (net (code "57") (name "Net-(R17-Pad2)") (class "Default")
      (node (ref "R17") (pin "2") (pinfunction "2_2") (pintype "passive"))
      (node (ref "SW1") (pin "B'") (pinfunction "B'_B'") (pintype "passive"))
    )
    (net (code "58") (name "Net-(R18-Pad2)") (class "Default")
      (node (ref "R18") (pin "2") (pinfunction "2_2") (pintype "passive"))
      (node (ref "SW2") (pin "B'") (pinfunction "B'_B'") (pintype "passive"))
    )
    (net (code "59") (name "Net-(R20-Pad2)") (class "Default")
      (node (ref "R20") (pin "2") (pinfunction "2_2") (pintype "passive"))
      (node (ref "SW3") (pin "B'") (pinfunction "B'_B'") (pintype "passive"))
    )
    (net (code "60") (name "Net-(R21-Pad2)") (class "Default")
      (node (ref "R21") (pin "2") (pinfunction "2_2") (pintype "passive"))
      (node (ref "SW4") (pin "B'") (pinfunction "B'_B'") (pintype "passive"))
    )
    (net (code "61") (name "Net-(R24-Pad2)") (class "Default")
      (node (ref "R24") (pin "2") (pinfunction "2_2") (pintype "passive"))
      (node (ref "SW5") (pin "B'") (pinfunction "B'_B'") (pintype "passive"))
    )
    (net (code "62") (name "Net-(SW_PWR-Pad3)") (class "Default")
      (node (ref "SW_PWR") (pin "3") (pinfunction "3_3") (pintype "passive"))
      (node (ref "Vin_JST") (pin "1") (pinfunction "1_1") (pintype "passive"))
    )
    (net (code "63") (name "unconnected-(BOOT-PadA)") (class "Default")
      (node (ref "BOOT") (pin "A") (pinfunction "A_A") (pintype "passive"))
    )
    (net (code "64") (name "unconnected-(BOOT-PadB')") (class "Default")
      (node (ref "BOOT") (pin "B'") (pinfunction "B'_B'") (pintype "passive"))
    )
    (net (code "65") (name "unconnected-(CP2102A-SUSPEND-Pad12)") (class "Default")
      (node (ref "CP2102") (pin "12") (pinfunction "SUSPEND_12") (pintype "output"))
    )
    (net (code "66") (name "unconnected-(CP2102A-~{CTS}-Pad23)") (class "Default")
      (node (ref "CP2102") (pin "23") (pinfunction "~{CTS}_23") (pintype "input+no_connect"))
    )
    (net (code "67") (name "unconnected-(CP2102A-~{DCD}-Pad1)") (class "Default")
      (node (ref "CP2102") (pin "1") (pinfunction "~{DCD}_1") (pintype "input+no_connect"))
    )
    (net (code "68") (name "unconnected-(CP2102A-~{DSR}-Pad27)") (class "Default")
      (node (ref "CP2102") (pin "27") (pinfunction "~{DSR}_27") (pintype "input+no_connect"))
    )
    (net (code "69") (name "unconnected-(CP2102A-~{DTR}-Pad28)") (class "Default")
      (node (ref "CP2102") (pin "28") (pinfunction "~{DTR}_28") (pintype "output"))
    )
    (net (code "70") (name "unconnected-(CP2102A-~{RI}-Pad2)") (class "Default")
      (node (ref "CP2102") (pin "2") (pinfunction "~{RI}_2") (pintype "input+no_connect"))
    )
    (net (code "71") (name "unconnected-(CP2102A-~{RTS}-Pad24)") (class "Default")
      (node (ref "CP2102") (pin "24") (pinfunction "~{RTS}_24") (pintype "output+no_connect"))
    )
    (net (code "72") (name "unconnected-(CP2102A-~{SUSPEND}-Pad11)") (class "Default")
      (node (ref "CP2102") (pin "11") (pinfunction "~{SUSPEND}_11") (pintype "output"))
    )
    (net (code "73") (name "unconnected-(ESP32 S3-IO3-Pad15)") (class "Default")
      (node (ref "ESP32 S3") (pin "15") (pinfunction "IO3_15") (pintype "bidirectional+no_connect"))
    )
    (net (code "74") (name "unconnected-(ESP32 S3-IO8-Pad12)") (class "Default")
      (node (ref "ESP32 S3") (pin "12") (pinfunction "IO8_12") (pintype "bidirectional"))
    )
    (net (code "75") (name "unconnected-(ESP32 S3-IO21-Pad23)") (class "Default")
      (node (ref "ESP32 S3") (pin "23") (pinfunction "IO21_23") (pintype "bidirectional"))
    )
    (net (code "76") (name "unconnected-(ESP32 S3-IO42-Pad35)") (class "Default")
      (node (ref "ESP32 S3") (pin "35") (pinfunction "IO42_35") (pintype "bidirectional"))
    )
    (net (code "77") (name "unconnected-(ESP32 S3-IO45-Pad26)") (class "Default")
      (node (ref "ESP32 S3") (pin "26") (pinfunction "IO45_26") (pintype "bidirectional+no_connect"))
    )
    (net (code "78") (name "unconnected-(ESP32 S3-IO46-Pad16)") (class "Default")
      (node (ref "ESP32 S3") (pin "16") (pinfunction "IO46_16") (pintype "bidirectional+no_connect"))
    )
    (net (code "79") (name "unconnected-(ESP32 S3-IO47-Pad24)") (class "Default")
      (node (ref "ESP32 S3") (pin "24") (pinfunction "IO47_24") (pintype "bidirectional"))
    )
    (net (code "80") (name "unconnected-(ESP32 S3-IO48-Pad25)") (class "Default")
      (node (ref "ESP32 S3") (pin "25") (pinfunction "IO48_25") (pintype "bidirectional"))
    )
    (net (code "81") (name "unconnected-(JOY1-MNT_1-Pad1)") (class "Default")
      (node (ref "JOY1") (pin "1") (pinfunction "MNT_1_1") (pintype "passive"))
    )
    (net (code "82") (name "unconnected-(JOY1-MNT_2-Pad2)") (class "Default")
      (node (ref "JOY1") (pin "2") (pinfunction "MNT_2_2") (pintype "passive"))
    )
    (net (code "83") (name "unconnected-(JOY1-MNT_3-Pad3)") (class "Default")
      (node (ref "JOY1") (pin "3") (pinfunction "MNT_3_3") (pintype "passive"))
    )
    (net (code "84") (name "unconnected-(JOY1-MNT_4-Pad4)") (class "Default")
      (node (ref "JOY1") (pin "4") (pinfunction "MNT_4_4") (pintype "passive"))
    )
    (net (code "85") (name "unconnected-(JOY1-Pada)") (class "Default")
      (node (ref "JOY1") (pin "a") (pinfunction "a_a") (pintype "passive"))
    )
    (net (code "86") (name "unconnected-(JOY2-MNT_1-Pad1)") (class "Default")
      (node (ref "JOY2") (pin "1") (pinfunction "MNT_1_1") (pintype "passive"))
    )
    (net (code "87") (name "unconnected-(JOY2-MNT_2-Pad2)") (class "Default")
      (node (ref "JOY2") (pin "2") (pinfunction "MNT_2_2") (pintype "passive"))
    )
    (net (code "88") (name "unconnected-(JOY2-MNT_3-Pad3)") (class "Default")
      (node (ref "JOY2") (pin "3") (pinfunction "MNT_3_3") (pintype "passive"))
    )
    (net (code "89") (name "unconnected-(JOY2-MNT_4-Pad4)") (class "Default")
      (node (ref "JOY2") (pin "4") (pinfunction "MNT_4_4") (pintype "passive"))
    )
    (net (code "90") (name "unconnected-(JOY2-Pada)") (class "Default")
      (node (ref "JOY2") (pin "a") (pinfunction "a_a") (pintype "passive"))
    )
    (net (code "91") (name "unconnected-(JOY3-MNT_1-Pad1)") (class "Default")
      (node (ref "JOY3") (pin "1") (pinfunction "MNT_1_1") (pintype "passive"))
    )
    (net (code "92") (name "unconnected-(JOY3-MNT_2-Pad2)") (class "Default")
      (node (ref "JOY3") (pin "2") (pinfunction "MNT_2_2") (pintype "passive"))
    )
    (net (code "93") (name "unconnected-(JOY3-MNT_3-Pad3)") (class "Default")
      (node (ref "JOY3") (pin "3") (pinfunction "MNT_3_3") (pintype "passive"))
    )
    (net (code "94") (name "unconnected-(JOY3-MNT_4-Pad4)") (class "Default")
      (node (ref "JOY3") (pin "4") (pinfunction "MNT_4_4") (pintype "passive"))
    )
    (net (code "95") (name "unconnected-(JOY3-Pada)") (class "Default")
      (node (ref "JOY3") (pin "a") (pinfunction "a_a") (pintype "passive"))
    )
    (net (code "96") (name "unconnected-(JOY4-MNT_1-Pad1)") (class "Default")
      (node (ref "JOY4") (pin "1") (pinfunction "MNT_1_1") (pintype "passive"))
    )
    (net (code "97") (name "unconnected-(JOY4-MNT_2-Pad2)") (class "Default")
      (node (ref "JOY4") (pin "2") (pinfunction "MNT_2_2") (pintype "passive"))
    )
    (net (code "98") (name "unconnected-(JOY4-MNT_3-Pad3)") (class "Default")
      (node (ref "JOY4") (pin "3") (pinfunction "MNT_3_3") (pintype "passive"))
    )
    (net (code "99") (name "unconnected-(JOY4-MNT_4-Pad4)") (class "Default")
      (node (ref "JOY4") (pin "4") (pinfunction "MNT_4_4") (pintype "passive"))
    )
    (net (code "100") (name "unconnected-(JOY4-Pada)") (class "Default")
      (node (ref "JOY4") (pin "a") (pinfunction "a_a") (pintype "passive"))
    )
    (net (code "101") (name "unconnected-(LoRa-DI01-Pad6)") (class "Default")
      (node (ref "LoRa") (pin "6") (pinfunction "DI01_6") (pintype "bidirectional"))
    )
    (net (code "102") (name "unconnected-(LoRa-DI02-Pad7)") (class "Default")
      (node (ref "LoRa") (pin "7") (pinfunction "DI02_7") (pintype "bidirectional"))
    )
    (net (code "103") (name "unconnected-(LoRa-DI03-Pad8)") (class "Default")
      (node (ref "LoRa") (pin "8") (pinfunction "DI03_8") (pintype "bidirectional"))
    )
    (net (code "104") (name "unconnected-(LoRa-DI04-Pad10)") (class "Default")
      (node (ref "LoRa") (pin "10") (pinfunction "DI04_10") (pintype "bidirectional"))
    )
    (net (code "105") (name "unconnected-(LoRa-DI05-Pad11)") (class "Default")
      (node (ref "LoRa") (pin "11") (pinfunction "DI05_11") (pintype "bidirectional"))
    )
    (net (code "106") (name "unconnected-(RESET-PadA)") (class "Default")
      (node (ref "RESET") (pin "A") (pinfunction "A_A") (pintype "passive"))
    )
    (net (code "107") (name "unconnected-(RESET-PadB)") (class "Default")
      (node (ref "RESET") (pin "B") (pinfunction "B_B") (pintype "passive"))
    )
    (net (code "108") (name "unconnected-(SW1-PadA')") (class "Default")
      (node (ref "SW1") (pin "A'") (pinfunction "A'_A'") (pintype "passive"))
    )
    (net (code "109") (name "unconnected-(SW2-PadA')") (class "Default")
      (node (ref "SW2") (pin "A'") (pinfunction "A'_A'") (pintype "passive"))
    )
    (net (code "110") (name "unconnected-(SW3-PadA')") (class "Default")
      (node (ref "SW3") (pin "A'") (pinfunction "A'_A'") (pintype "passive"))
    )
    (net (code "111") (name "unconnected-(SW4-PadA')") (class "Default")
      (node (ref "SW4") (pin "A'") (pinfunction "A'_A'") (pintype "passive"))
    )
    (net (code "112") (name "unconnected-(SW5-PadA')") (class "Default")
      (node (ref "SW5") (pin "A'") (pinfunction "A'_A'") (pintype "passive"))
    )
    (net (code "113") (name "unconnected-(UART-ID-Pad4)") (class "Default")
      (node (ref "UART") (pin "4") (pinfunction "ID_4") (pintype "passive"))
    )
    (net (code "114") (name "unconnected-(USB micro B-ID-Pad4)") (class "Default")
      (node (ref "USB micro B") (pin "4") (pinfunction "ID_4") (pintype "passive"))
    )
    (net (code "115") (name "unconnected-(USB micro B-VBUS-Pad1)") (class "Default")
      (node (ref "USB micro B") (pin "1") (pinfunction "VBUS_1") (pintype "passive"))
    )
  )
)
